# QCLogic_Rev_A_Sht1_MCU_IO.net
KiCad netlist of a schematic drawn in Altium Designer
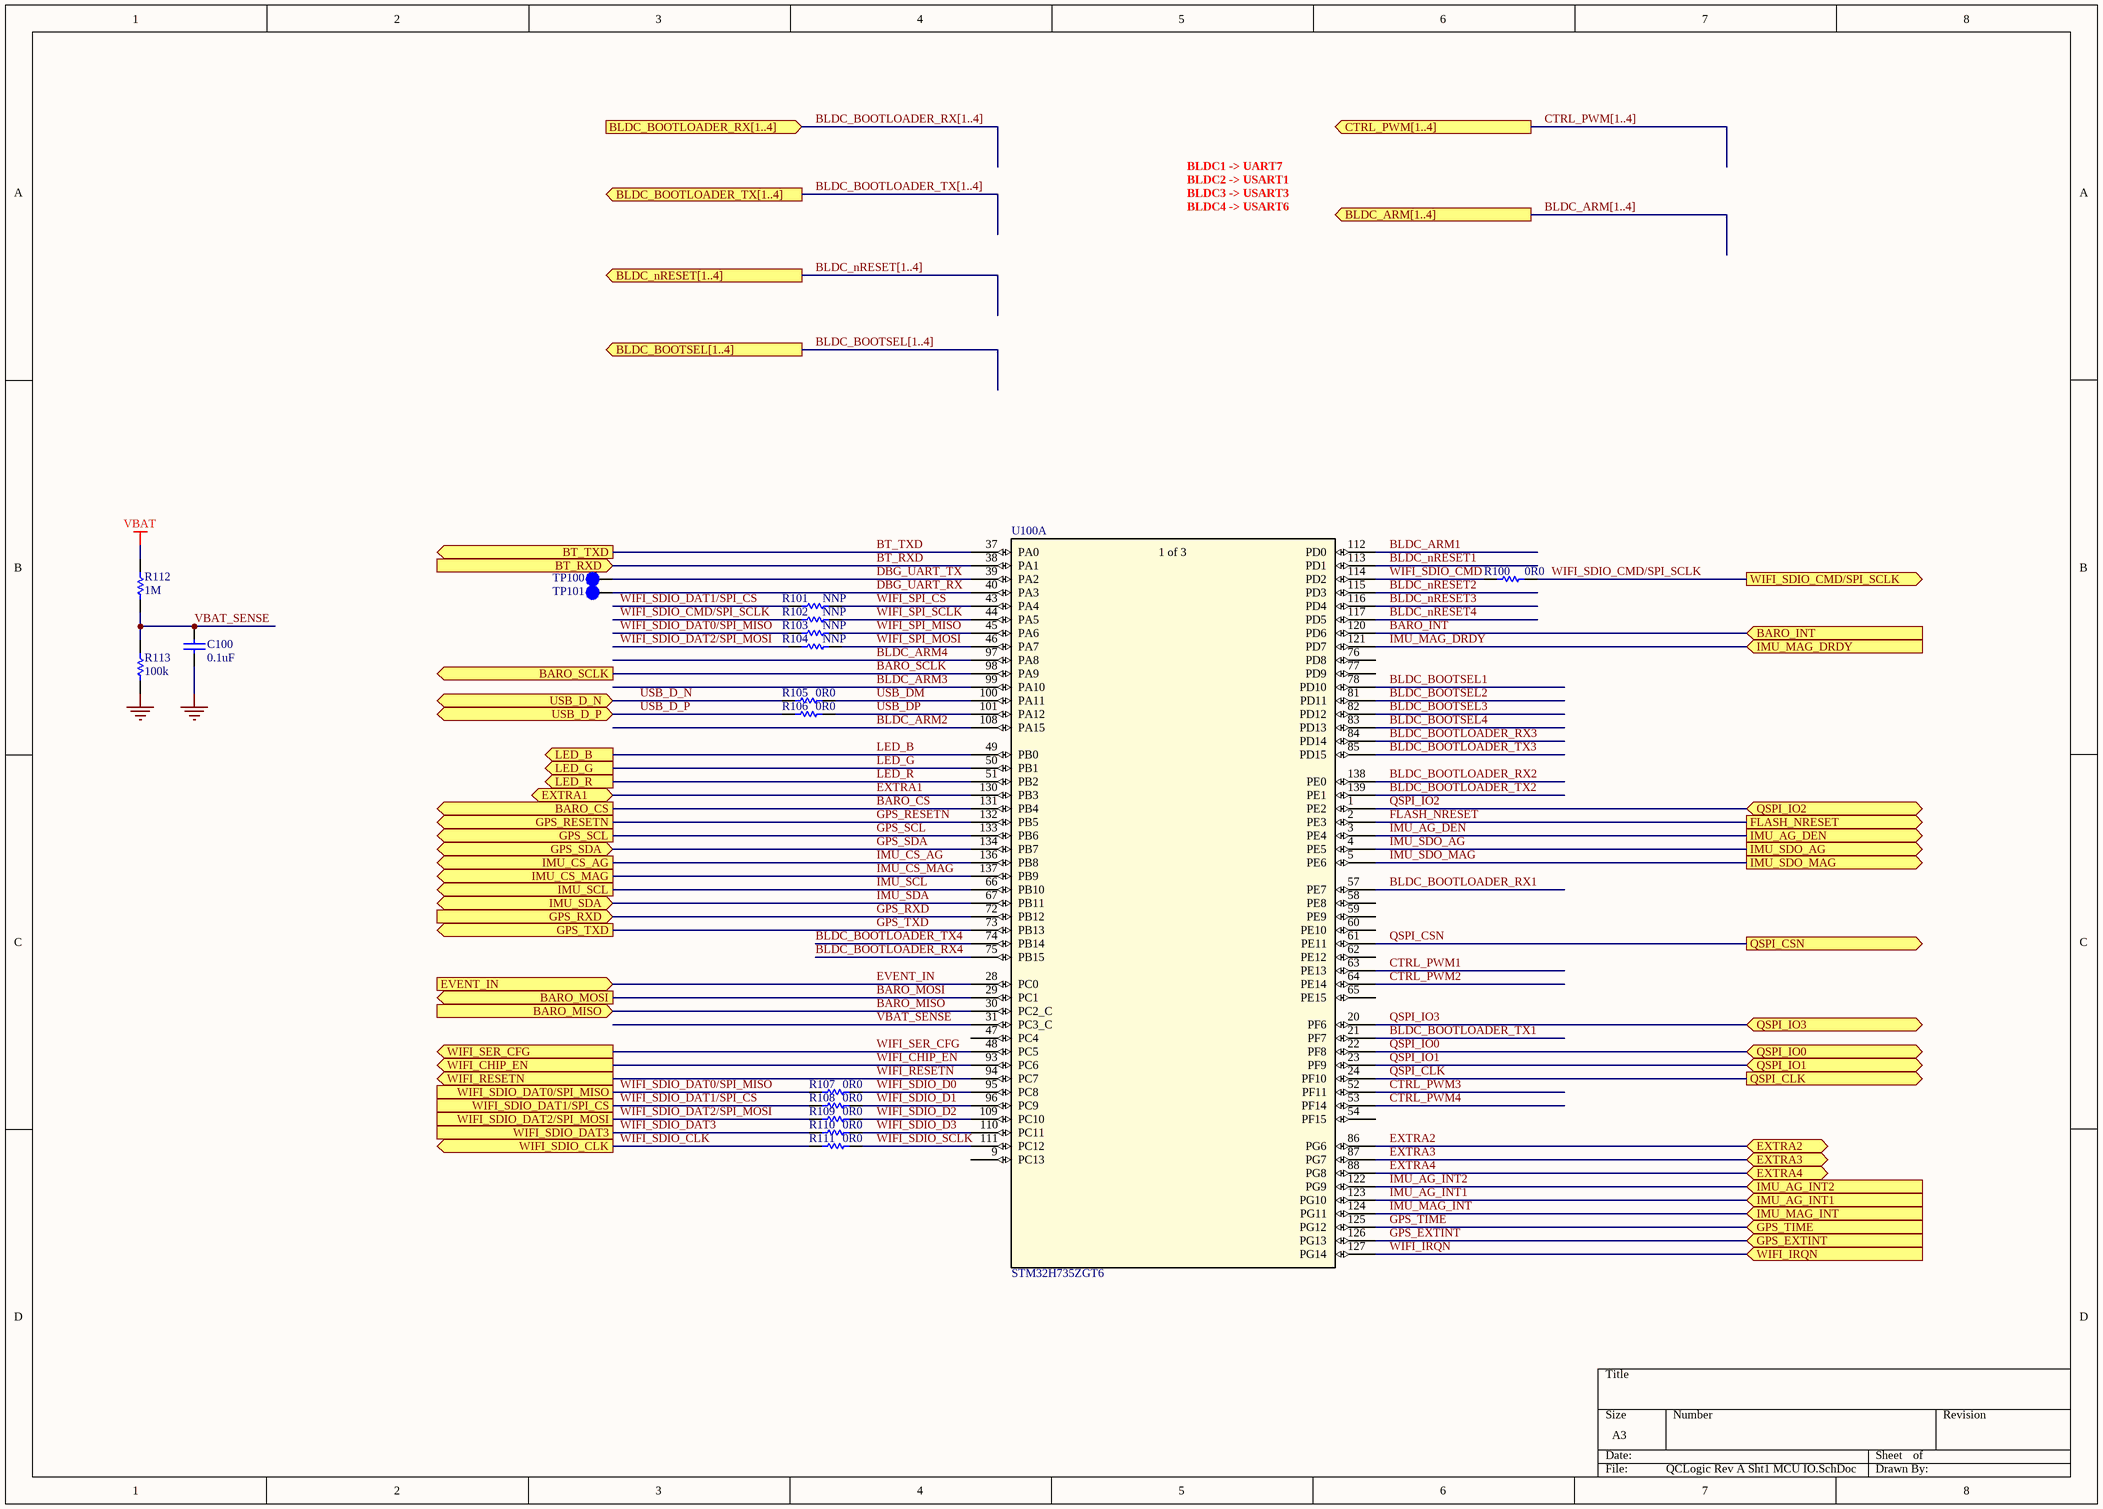
[diagram p0: QCLogic Rev A Sht1 MCU IO.SchDoc]

(export (version "E")
  (design (tool "Eeschema 10.0.6"))
  (components
    (comp (ref "C100")
      (value "0.1uF")
      (footprint "SMD CAP 0402")
      (description "CAP CER 0.1UF 25V X7R 0402")
      (fields (field (name "2. MANUFACTURER PART NUMBER") "CC0402KRX7R8BB104"))
      (libsource (lib "SBCLib") (part "CAP MLCC SMD"))
    )
    (comp (ref "R100")
      (value "0R0")
      (footprint "SMD RES 0402")
      (description "RES SMD 0 OHM JUMPER 1/16W 0402")
      (fields (field (name "2. MANUFACTURER PART NUMBER") "RC0402FR-070RL"))
      (libsource (lib "SBCLib") (part "RES SMD"))
    )
    (comp (ref "R101")
      (value "NNP")
      (footprint "SMD RES 0402")
      (description "RES SMD 0 OHM JUMPER 1/16W 0402")
      (fields (field (name "2. MANUFACTURER PART NUMBER") "RC0402FR-070RL"))
      (libsource (lib "SBCLib") (part "RES SMD"))
    )
    (comp (ref "R102")
      (value "NNP")
      (footprint "SMD RES 0402")
      (description "RES SMD 0 OHM JUMPER 1/16W 0402")
      (fields (field (name "2. MANUFACTURER PART NUMBER") "RC0402FR-070RL"))
      (libsource (lib "SBCLib") (part "RES SMD"))
    )
    (comp (ref "R103")
      (value "NNP")
      (footprint "SMD RES 0402")
      (description "RES SMD 0 OHM JUMPER 1/16W 0402")
      (fields (field (name "2. MANUFACTURER PART NUMBER") "RC0402FR-070RL"))
      (libsource (lib "SBCLib") (part "RES SMD"))
    )
    (comp (ref "R104")
      (value "NNP")
      (footprint "SMD RES 0402")
      (description "RES SMD 0 OHM JUMPER 1/16W 0402")
      (fields (field (name "2. MANUFACTURER PART NUMBER") "RC0402FR-070RL"))
      (libsource (lib "SBCLib") (part "RES SMD"))
    )
    (comp (ref "R105")
      (value "0R0")
      (footprint "SMD RES 0402")
      (description "RES SMD 0 OHM JUMPER 1/16W 0402")
      (fields (field (name "2. MANUFACTURER PART NUMBER") "RC0402FR-070RL"))
      (libsource (lib "SBCLib") (part "RES SMD"))
    )
    (comp (ref "R106")
      (value "0R0")
      (footprint "SMD RES 0402")
      (description "RES SMD 0 OHM JUMPER 1/16W 0402")
      (fields (field (name "2. MANUFACTURER PART NUMBER") "RC0402FR-070RL"))
      (libsource (lib "SBCLib") (part "RES SMD"))
    )
    (comp (ref "R107")
      (value "0R0")
      (footprint "SMD RES 0402")
      (description "RES SMD 0 OHM JUMPER 1/16W 0402")
      (fields (field (name "2. MANUFACTURER PART NUMBER") "RC0402FR-070RL"))
      (libsource (lib "SBCLib") (part "RES SMD"))
    )
    (comp (ref "R108")
      (value "0R0")
      (footprint "SMD RES 0402")
      (description "RES SMD 0 OHM JUMPER 1/16W 0402")
      (fields (field (name "2. MANUFACTURER PART NUMBER") "RC0402FR-070RL"))
      (libsource (lib "SBCLib") (part "RES SMD"))
    )
    (comp (ref "R109")
      (value "0R0")
      (footprint "SMD RES 0402")
      (description "RES SMD 0 OHM JUMPER 1/16W 0402")
      (fields (field (name "2. MANUFACTURER PART NUMBER") "RC0402FR-070RL"))
      (libsource (lib "SBCLib") (part "RES SMD"))
    )
    (comp (ref "R110")
      (value "0R0")
      (footprint "SMD RES 0402")
      (description "RES SMD 0 OHM JUMPER 1/16W 0402")
      (fields (field (name "2. MANUFACTURER PART NUMBER") "RC0402FR-070RL"))
      (libsource (lib "SBCLib") (part "RES SMD"))
    )
    (comp (ref "R111")
      (value "0R0")
      (footprint "SMD RES 0402")
      (description "RES SMD 0 OHM JUMPER 1/16W 0402")
      (fields (field (name "2. MANUFACTURER PART NUMBER") "RC0402FR-070RL"))
      (libsource (lib "SBCLib") (part "RES SMD"))
    )
    (comp (ref "R112")
      (value "1M")
      (footprint "SMD RES 0402")
      (description "RES SMD 1M OHM 1% 1/16W 0402")
      (fields (field (name "2. MANUFACTURER PART NUMBER") "RC0402FR-071ML"))
      (libsource (lib "SBCLib") (part "RES SMD"))
    )
    (comp (ref "R113")
      (value "100k")
      (footprint "SMD RES 0402")
      (description "RES SMD 100K OHM 1% 1/16W 0402")
      (fields (field (name "2. MANUFACTURER PART NUMBER") "RC0402FR-07100KL"))
      (libsource (lib "SBCLib") (part "RES SMD"))
    )
    (comp (ref "TP100")
      (value "TESTPOINT SMD")
      (footprint "TESTPOINT 1mm DIA")
      (description "TESTPOINT SMD PAD")
      (libsource (lib "SBCLib") (part "TESTPOINT PAD"))
    )
    (comp (ref "TP101")
      (value "TESTPOINT SMD")
      (footprint "TESTPOINT 1mm DIA")
      (description "TESTPOINT SMD PAD")
      (libsource (lib "SBCLib") (part "TESTPOINT PAD"))
    )
    (comp (ref "U100")
      (value "STM32H735ZGT6")
      (footprint "LQFP-144 20x20")
      (description "ARM® Cortex®-M7 STM32H7 Microcontroller IC 32-Bit 550MHz 1MB (1M x 8) FLASH 144 LQFP 20x20")
      (libsource (lib "SBCLib") (part "IC MCU STM32H735ZG Arm M7"))
    )
  )
  (nets
    (net (code "1") (name "/BARO_CS") (class "Default")
      (node (ref "U100") (pin "131") (pinfunction "PB4_131") (pintype "bidirectional"))
    )
    (net (code "2") (name "/BARO_INT") (class "Default")
      (node (ref "U100") (pin "120") (pinfunction "PD6_120") (pintype "bidirectional"))
    )
    (net (code "3") (name "/BARO_MISO") (class "Default")
      (node (ref "U100") (pin "30") (pinfunction "PC2_C_30") (pintype "bidirectional"))
    )
    (net (code "4") (name "/BARO_MOSI") (class "Default")
      (node (ref "U100") (pin "29") (pinfunction "PC1_29") (pintype "bidirectional"))
    )
    (net (code "5") (name "/BARO_SCLK") (class "Default")
      (node (ref "U100") (pin "98") (pinfunction "PA9_98") (pintype "bidirectional"))
    )
    (net (code "6") (name "/BLDC_ARM1") (class "Default")
      (node (ref "U100") (pin "112") (pinfunction "PD0_112") (pintype "bidirectional"))
    )
    (net (code "7") (name "/BLDC_ARM2") (class "Default")
      (node (ref "U100") (pin "108") (pinfunction "PA15_108") (pintype "bidirectional"))
    )
    (net (code "8") (name "/BLDC_ARM3") (class "Default")
      (node (ref "U100") (pin "99") (pinfunction "PA10_99") (pintype "bidirectional"))
    )
    (net (code "9") (name "/BLDC_ARM4") (class "Default")
      (node (ref "U100") (pin "97") (pinfunction "PA8_97") (pintype "bidirectional"))
    )
    (net (code "11") (name "/BLDC_BOOTLOADER_RX1") (class "Default")
      (node (ref "U100") (pin "57") (pinfunction "PE7_57") (pintype "bidirectional"))
    )
    (net (code "12") (name "/BLDC_BOOTLOADER_RX2") (class "Default")
      (node (ref "U100") (pin "138") (pinfunction "PE0_138") (pintype "bidirectional"))
    )
    (net (code "13") (name "/BLDC_BOOTLOADER_RX3") (class "Default")
      (node (ref "U100") (pin "84") (pinfunction "PD14_84") (pintype "bidirectional"))
    )
    (net (code "14") (name "/BLDC_BOOTLOADER_RX4") (class "Default")
      (node (ref "U100") (pin "75") (pinfunction "PB15_75") (pintype "bidirectional"))
    )
    (net (code "16") (name "/BLDC_BOOTLOADER_TX1") (class "Default")
      (node (ref "U100") (pin "21") (pinfunction "PF7_21") (pintype "bidirectional"))
    )
    (net (code "17") (name "/BLDC_BOOTLOADER_TX2") (class "Default")
      (node (ref "U100") (pin "139") (pinfunction "PE1_139") (pintype "bidirectional"))
    )
    (net (code "18") (name "/BLDC_BOOTLOADER_TX3") (class "Default")
      (node (ref "U100") (pin "85") (pinfunction "PD15_85") (pintype "bidirectional"))
    )
    (net (code "19") (name "/BLDC_BOOTLOADER_TX4") (class "Default")
      (node (ref "U100") (pin "74") (pinfunction "PB14_74") (pintype "bidirectional"))
    )
    (net (code "21") (name "/BLDC_BOOTSEL1") (class "Default")
      (node (ref "U100") (pin "78") (pinfunction "PD10_78") (pintype "bidirectional"))
    )
    (net (code "22") (name "/BLDC_BOOTSEL2") (class "Default")
      (node (ref "U100") (pin "81") (pinfunction "PD11_81") (pintype "bidirectional"))
    )
    (net (code "23") (name "/BLDC_BOOTSEL3") (class "Default")
      (node (ref "U100") (pin "82") (pinfunction "PD12_82") (pintype "bidirectional"))
    )
    (net (code "24") (name "/BLDC_BOOTSEL4") (class "Default")
      (node (ref "U100") (pin "83") (pinfunction "PD13_83") (pintype "bidirectional"))
    )
    (net (code "26") (name "/BLDC_nRESET1") (class "Default")
      (node (ref "U100") (pin "113") (pinfunction "PD1_113") (pintype "bidirectional"))
    )
    (net (code "27") (name "/BLDC_nRESET2") (class "Default")
      (node (ref "U100") (pin "115") (pinfunction "PD3_115") (pintype "bidirectional"))
    )
    (net (code "28") (name "/BLDC_nRESET3") (class "Default")
      (node (ref "U100") (pin "116") (pinfunction "PD4_116") (pintype "bidirectional"))
    )
    (net (code "29") (name "/BLDC_nRESET4") (class "Default")
      (node (ref "U100") (pin "117") (pinfunction "PD5_117") (pintype "bidirectional"))
    )
    (net (code "31") (name "/BT_RXD") (class "Default")
      (node (ref "U100") (pin "38") (pinfunction "PA1_38") (pintype "bidirectional"))
    )
    (net (code "32") (name "/BT_TXD") (class "Default")
      (node (ref "U100") (pin "37") (pinfunction "PA0_37") (pintype "bidirectional"))
    )
    (net (code "33") (name "/CTRL_PWM1") (class "Default")
      (node (ref "U100") (pin "63") (pinfunction "PE13_63") (pintype "bidirectional"))
    )
    (net (code "34") (name "/CTRL_PWM2") (class "Default")
      (node (ref "U100") (pin "64") (pinfunction "PE14_64") (pintype "bidirectional"))
    )
    (net (code "35") (name "/CTRL_PWM3") (class "Default")
      (node (ref "U100") (pin "52") (pinfunction "PF11_52") (pintype "bidirectional"))
    )
    (net (code "36") (name "/CTRL_PWM4") (class "Default")
      (node (ref "U100") (pin "53") (pinfunction "PF14_53") (pintype "bidirectional"))
    )
    (net (code "38") (name "/DBG_UART_RX") (class "Default")
      (node (ref "TP101") (pin "1") (pinfunction "1_1") (pintype "passive"))
      (node (ref "U100") (pin "40") (pinfunction "PA3_40") (pintype "bidirectional"))
    )
    (net (code "39") (name "/DBG_UART_TX") (class "Default")
      (node (ref "TP100") (pin "1") (pinfunction "1_1") (pintype "passive"))
      (node (ref "U100") (pin "39") (pinfunction "PA2_39") (pintype "bidirectional"))
    )
    (net (code "40") (name "/EVENT_IN") (class "Default")
      (node (ref "U100") (pin "28") (pinfunction "PC0_28") (pintype "bidirectional"))
    )
    (net (code "41") (name "/EXTRA1") (class "Default")
      (node (ref "U100") (pin "130") (pinfunction "PB3_130") (pintype "bidirectional"))
    )
    (net (code "42") (name "/EXTRA2") (class "Default")
      (node (ref "U100") (pin "86") (pinfunction "PG6_86") (pintype "bidirectional"))
    )
    (net (code "43") (name "/EXTRA3") (class "Default")
      (node (ref "U100") (pin "87") (pinfunction "PG7_87") (pintype "bidirectional"))
    )
    (net (code "44") (name "/EXTRA4") (class "Default")
      (node (ref "U100") (pin "88") (pinfunction "PG8_88") (pintype "bidirectional"))
    )
    (net (code "45") (name "/FLASH_NRESET") (class "Default")
      (node (ref "U100") (pin "2") (pinfunction "PE3_2") (pintype "bidirectional"))
    )
    (net (code "46") (name "/GPS_EXTINT") (class "Default")
      (node (ref "U100") (pin "126") (pinfunction "PG13_126") (pintype "bidirectional"))
    )
    (net (code "47") (name "/GPS_RESETN") (class "Default")
      (node (ref "U100") (pin "132") (pinfunction "PB5_132") (pintype "bidirectional"))
    )
    (net (code "48") (name "/GPS_RXD") (class "Default")
      (node (ref "U100") (pin "72") (pinfunction "PB12_72") (pintype "bidirectional"))
    )
    (net (code "49") (name "/GPS_SCL") (class "Default")
      (node (ref "U100") (pin "133") (pinfunction "PB6_133") (pintype "bidirectional"))
    )
    (net (code "50") (name "/GPS_SDA") (class "Default")
      (node (ref "U100") (pin "134") (pinfunction "PB7_134") (pintype "bidirectional"))
    )
    (net (code "51") (name "/GPS_TIME") (class "Default")
      (node (ref "U100") (pin "125") (pinfunction "PG12_125") (pintype "bidirectional"))
    )
    (net (code "52") (name "/GPS_TXD") (class "Default")
      (node (ref "U100") (pin "73") (pinfunction "PB13_73") (pintype "bidirectional"))
    )
    (net (code "53") (name "/IMU_AG_DEN") (class "Default")
      (node (ref "U100") (pin "3") (pinfunction "PE4_3") (pintype "bidirectional"))
    )
    (net (code "54") (name "/IMU_AG_INT1") (class "Default")
      (node (ref "U100") (pin "123") (pinfunction "PG10_123") (pintype "bidirectional"))
    )
    (net (code "55") (name "/IMU_AG_INT2") (class "Default")
      (node (ref "U100") (pin "122") (pinfunction "PG9_122") (pintype "bidirectional"))
    )
    (net (code "56") (name "/IMU_CS_AG") (class "Default")
      (node (ref "U100") (pin "136") (pinfunction "PB8_136") (pintype "bidirectional"))
    )
    (net (code "57") (name "/IMU_CS_MAG") (class "Default")
      (node (ref "U100") (pin "137") (pinfunction "PB9_137") (pintype "bidirectional"))
    )
    (net (code "58") (name "/IMU_MAG_DRDY") (class "Default")
      (node (ref "U100") (pin "121") (pinfunction "PD7_121") (pintype "bidirectional"))
    )
    (net (code "59") (name "/IMU_MAG_INT") (class "Default")
      (node (ref "U100") (pin "124") (pinfunction "PG11_124") (pintype "bidirectional"))
    )
    (net (code "60") (name "/IMU_SCL") (class "Default")
      (node (ref "U100") (pin "66") (pinfunction "PB10_66") (pintype "bidirectional"))
    )
    (net (code "61") (name "/IMU_SDA") (class "Default")
      (node (ref "U100") (pin "67") (pinfunction "PB11_67") (pintype "bidirectional"))
    )
    (net (code "62") (name "/IMU_SDO_AG") (class "Default")
      (node (ref "U100") (pin "4") (pinfunction "PE5_4") (pintype "bidirectional"))
    )
    (net (code "63") (name "/IMU_SDO_MAG") (class "Default")
      (node (ref "U100") (pin "5") (pinfunction "PE6_5") (pintype "bidirectional"))
    )
    (net (code "64") (name "/LED_B") (class "Default")
      (node (ref "U100") (pin "49") (pinfunction "PB0_49") (pintype "bidirectional"))
    )
    (net (code "65") (name "/LED_G") (class "Default")
      (node (ref "U100") (pin "50") (pinfunction "PB1_50") (pintype "bidirectional"))
    )
    (net (code "66") (name "/LED_R") (class "Default")
      (node (ref "U100") (pin "51") (pinfunction "PB2_51") (pintype "bidirectional"))
    )
    (net (code "67") (name "/QSPI_CLK") (class "Default")
      (node (ref "U100") (pin "24") (pinfunction "PF10_24") (pintype "bidirectional"))
    )
    (net (code "68") (name "/QSPI_CSN") (class "Default")
      (node (ref "U100") (pin "61") (pinfunction "PE11_61") (pintype "bidirectional"))
    )
    (net (code "69") (name "/QSPI_IO0") (class "Default")
      (node (ref "U100") (pin "22") (pinfunction "PF8_22") (pintype "bidirectional"))
    )
    (net (code "70") (name "/QSPI_IO1") (class "Default")
      (node (ref "U100") (pin "23") (pinfunction "PF9_23") (pintype "bidirectional"))
    )
    (net (code "71") (name "/QSPI_IO2") (class "Default")
      (node (ref "U100") (pin "1") (pinfunction "PE2_1") (pintype "bidirectional"))
    )
    (net (code "72") (name "/QSPI_IO3") (class "Default")
      (node (ref "U100") (pin "20") (pinfunction "PF6_20") (pintype "bidirectional"))
    )
    (net (code "73") (name "/USB_DM") (class "Default")
      (node (ref "R105") (pin "2") (pinfunction "2_2") (pintype "passive"))
      (node (ref "U100") (pin "100") (pinfunction "PA11_100") (pintype "bidirectional"))
    )
    (net (code "74") (name "/USB_DP") (class "Default")
      (node (ref "R106") (pin "2") (pinfunction "2_2") (pintype "passive"))
      (node (ref "U100") (pin "101") (pinfunction "PA12_101") (pintype "bidirectional"))
    )
    (net (code "75") (name "/USB_D_N") (class "Default")
      (node (ref "R105") (pin "1") (pinfunction "1_1") (pintype "passive"))
    )
    (net (code "76") (name "/USB_D_P") (class "Default")
      (node (ref "R106") (pin "1") (pinfunction "1_1") (pintype "passive"))
    )
    (net (code "77") (name "/VBAT_SENSE") (class "Default")
      (node (ref "C100") (pin "2") (pinfunction "2_2") (pintype "passive"))
      (node (ref "R112") (pin "2") (pinfunction "2_2") (pintype "passive"))
      (node (ref "R113") (pin "1") (pinfunction "1_1") (pintype "passive"))
      (node (ref "U100") (pin "31") (pinfunction "PC3_C_31") (pintype "bidirectional"))
    )
    (net (code "78") (name "/WIFI_CHIP_EN") (class "Default")
      (node (ref "U100") (pin "93") (pinfunction "PC6_93") (pintype "bidirectional"))
    )
    (net (code "79") (name "/WIFI_IRQN") (class "Default")
      (node (ref "U100") (pin "127") (pinfunction "PG14_127") (pintype "bidirectional"))
    )
    (net (code "80") (name "/WIFI_RESETN") (class "Default")
      (node (ref "U100") (pin "94") (pinfunction "PC7_94") (pintype "bidirectional"))
    )
    (net (code "81") (name "/WIFI_SDIO_CLK") (class "Default")
      (node (ref "R111") (pin "1") (pinfunction "1_1") (pintype "passive"))
    )
    (net (code "82") (name "/WIFI_SDIO_CMD") (class "Default")
      (node (ref "R100") (pin "2") (pinfunction "2_2") (pintype "passive"))
      (node (ref "U100") (pin "114") (pinfunction "PD2_114") (pintype "bidirectional"))
    )
    (net (code "83") (name "/WIFI_SDIO_CMD{slash}SPI_SCLK") (class "Default")
      (node (ref "R100") (pin "1") (pinfunction "1_1") (pintype "passive"))
      (node (ref "R102") (pin "1") (pinfunction "1_1") (pintype "passive"))
    )
    (net (code "84") (name "/WIFI_SDIO_D0") (class "Default")
      (node (ref "R107") (pin "2") (pinfunction "2_2") (pintype "passive"))
      (node (ref "U100") (pin "95") (pinfunction "PC8_95") (pintype "bidirectional"))
    )
    (net (code "85") (name "/WIFI_SDIO_D1") (class "Default")
      (node (ref "R108") (pin "2") (pinfunction "2_2") (pintype "passive"))
      (node (ref "U100") (pin "96") (pinfunction "PC9_96") (pintype "bidirectional"))
    )
    (net (code "86") (name "/WIFI_SDIO_D2") (class "Default")
      (node (ref "R109") (pin "2") (pinfunction "2_2") (pintype "passive"))
      (node (ref "U100") (pin "109") (pinfunction "PC10_109") (pintype "bidirectional"))
    )
    (net (code "87") (name "/WIFI_SDIO_D3") (class "Default")
      (node (ref "R110") (pin "2") (pinfunction "2_2") (pintype "passive"))
      (node (ref "U100") (pin "110") (pinfunction "PC11_110") (pintype "bidirectional"))
    )
    (net (code "88") (name "/WIFI_SDIO_DAT0{slash}SPI_MISO") (class "Default")
      (node (ref "R103") (pin "1") (pinfunction "1_1") (pintype "passive"))
      (node (ref "R107") (pin "1") (pinfunction "1_1") (pintype "passive"))
    )
    (net (code "89") (name "/WIFI_SDIO_DAT1{slash}SPI_CS") (class "Default")
      (node (ref "R101") (pin "2") (pinfunction "2_2") (pintype "passive"))
      (node (ref "R108") (pin "1") (pinfunction "1_1") (pintype "passive"))
    )
    (net (code "90") (name "/WIFI_SDIO_DAT2{slash}SPI_MOSI") (class "Default")
      (node (ref "R104") (pin "1") (pinfunction "1_1") (pintype "passive"))
      (node (ref "R109") (pin "1") (pinfunction "1_1") (pintype "passive"))
    )
    (net (code "91") (name "/WIFI_SDIO_DAT3") (class "Default")
      (node (ref "R110") (pin "1") (pinfunction "1_1") (pintype "passive"))
    )
    (net (code "92") (name "/WIFI_SDIO_SCLK") (class "Default")
      (node (ref "R111") (pin "2") (pinfunction "2_2") (pintype "passive"))
      (node (ref "U100") (pin "111") (pinfunction "PC12_111") (pintype "bidirectional"))
    )
    (net (code "93") (name "/WIFI_SER_CFG") (class "Default")
      (node (ref "U100") (pin "48") (pinfunction "PC5_48") (pintype "bidirectional"))
    )
    (net (code "94") (name "/WIFI_SPI_CS") (class "Default")
      (node (ref "R101") (pin "1") (pinfunction "1_1") (pintype "passive"))
      (node (ref "U100") (pin "43") (pinfunction "PA4_43") (pintype "bidirectional"))
    )
    (net (code "95") (name "/WIFI_SPI_MISO") (class "Default")
      (node (ref "R103") (pin "2") (pinfunction "2_2") (pintype "passive"))
      (node (ref "U100") (pin "45") (pinfunction "PA6_45") (pintype "bidirectional"))
    )
    (net (code "96") (name "/WIFI_SPI_MOSI") (class "Default")
      (node (ref "R104") (pin "2") (pinfunction "2_2") (pintype "passive"))
      (node (ref "U100") (pin "46") (pinfunction "PA7_46") (pintype "bidirectional"))
    )
    (net (code "97") (name "/WIFI_SPI_SCLK") (class "Default")
      (node (ref "R102") (pin "2") (pinfunction "2_2") (pintype "passive"))
      (node (ref "U100") (pin "44") (pinfunction "PA5_44") (pintype "bidirectional"))
    )
    (net (code "98") (name "GND") (class "Default")
      (node (ref "C100") (pin "1") (pinfunction "1_1") (pintype "passive"))
      (node (ref "R113") (pin "2") (pinfunction "2_2") (pintype "passive"))
    )
    (net (code "99") (name "VBAT") (class "Default")
      (node (ref "R112") (pin "1") (pinfunction "1_1") (pintype "passive"))
    )
    (net (code "100") (name "unconnected-(U100A-PC4-Pad47)") (class "Default")
      (node (ref "U100") (pin "47") (pinfunction "PC4_47") (pintype "bidirectional"))
    )
    (net (code "101") (name "unconnected-(U100A-PC13-Pad9)") (class "Default")
      (node (ref "U100") (pin "9") (pinfunction "PC13_9") (pintype "bidirectional"))
    )
    (net (code "102") (name "unconnected-(U100A-PD8-Pad76)") (class "Default")
      (node (ref "U100") (pin "76") (pinfunction "PD8_76") (pintype "bidirectional"))
    )
    (net (code "103") (name "unconnected-(U100A-PD9-Pad77)") (class "Default")
      (node (ref "U100") (pin "77") (pinfunction "PD9_77") (pintype "bidirectional"))
    )
    (net (code "104") (name "unconnected-(U100A-PE8-Pad58)") (class "Default")
      (node (ref "U100") (pin "58") (pinfunction "PE8_58") (pintype "bidirectional"))
    )
    (net (code "105") (name "unconnected-(U100A-PE9-Pad59)") (class "Default")
      (node (ref "U100") (pin "59") (pinfunction "PE9_59") (pintype "bidirectional"))
    )
    (net (code "106") (name "unconnected-(U100A-PE10-Pad60)") (class "Default")
      (node (ref "U100") (pin "60") (pinfunction "PE10_60") (pintype "bidirectional"))
    )
    (net (code "107") (name "unconnected-(U100A-PE12-Pad62)") (class "Default")
      (node (ref "U100") (pin "62") (pinfunction "PE12_62") (pintype "bidirectional"))
    )
    (net (code "108") (name "unconnected-(U100A-PE15-Pad65)") (class "Default")
      (node (ref "U100") (pin "65") (pinfunction "PE15_65") (pintype "bidirectional"))
    )
    (net (code "109") (name "unconnected-(U100A-PF15-Pad54)") (class "Default")
      (node (ref "U100") (pin "54") (pinfunction "PF15_54") (pintype "bidirectional"))
    )
  )
)
